# PinballBumper_DaughterBoard.net
KiCad netlist of a schematic drawn in EAGLE
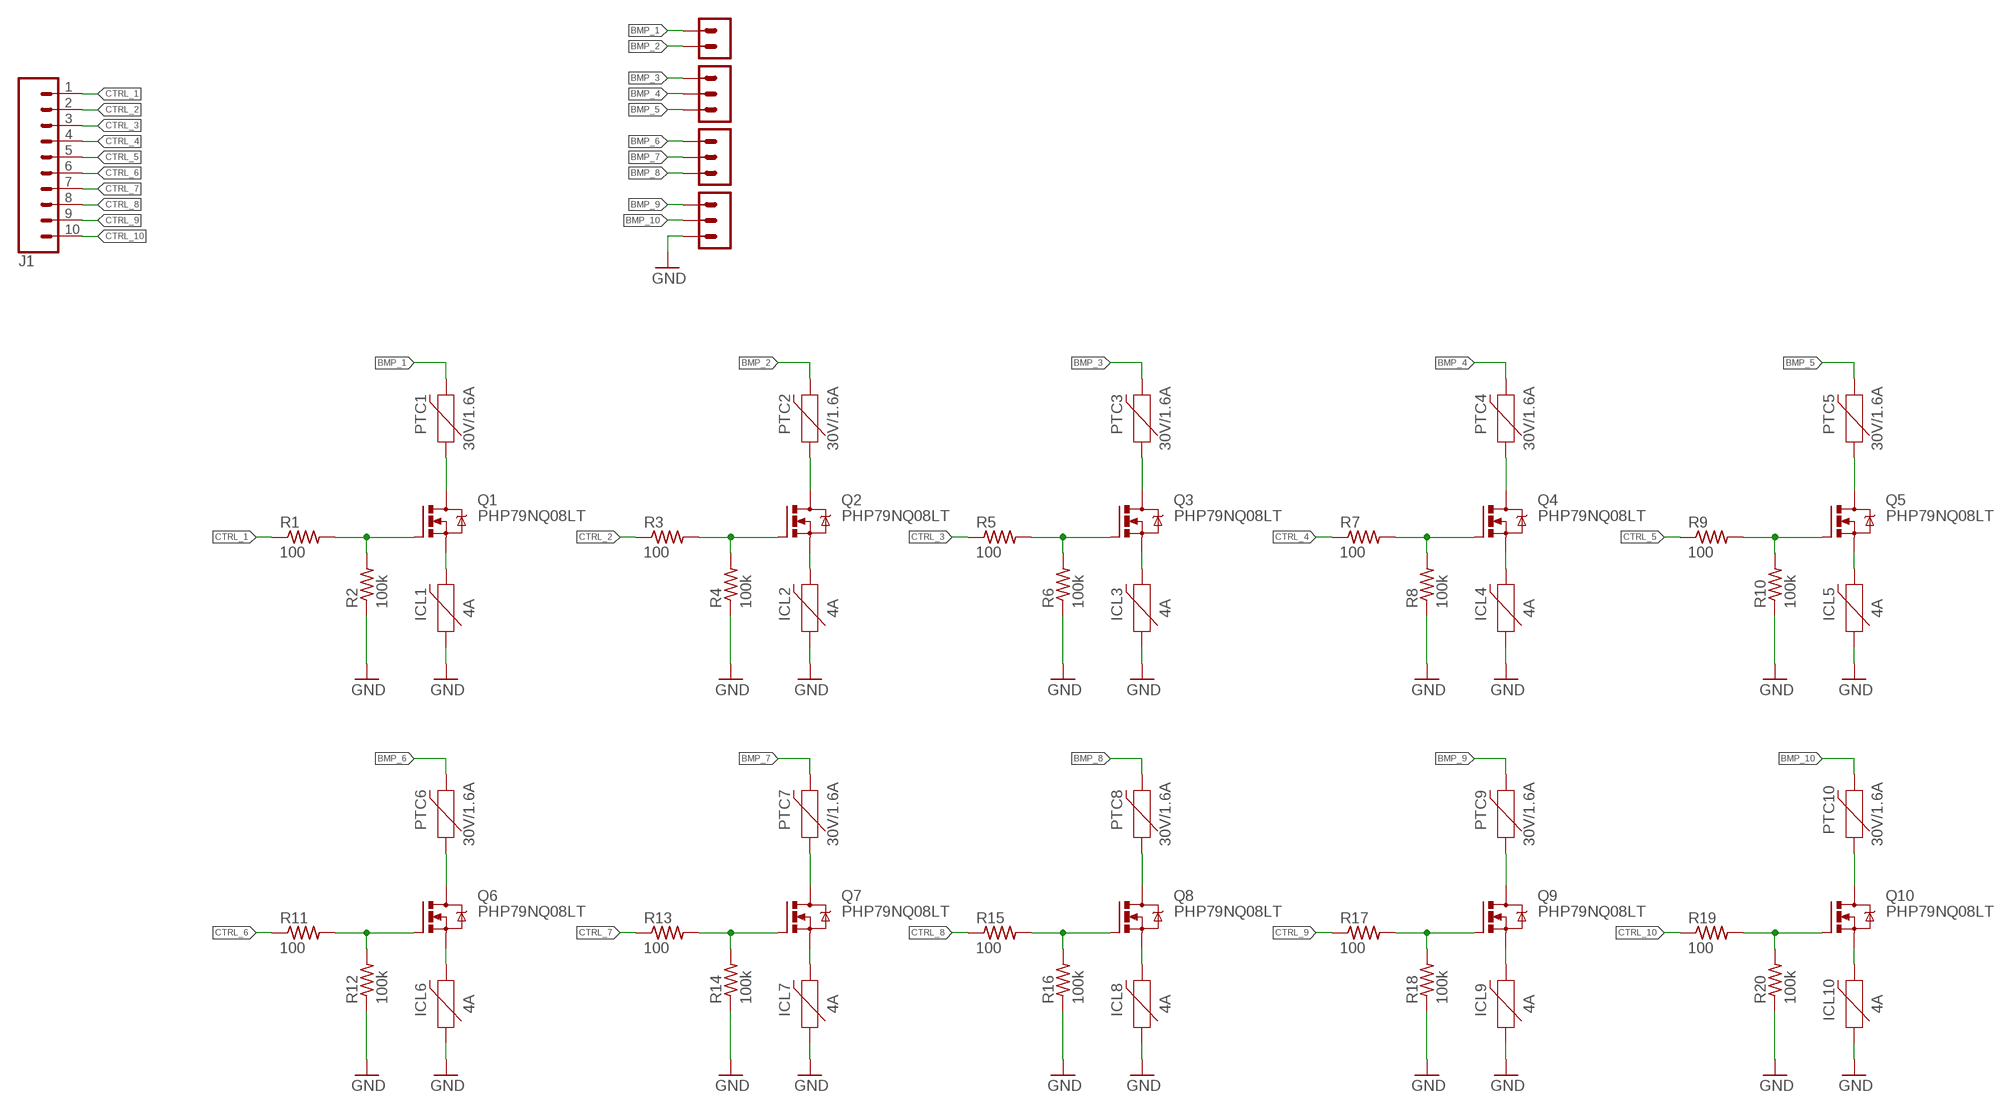
[diagram p0: schematic, sheet 1]

(export (version "E")
  (design (tool "Eeschema 10.0.6"))
  (components
    (comp (ref "ICL1")
      (value "4A")
      (footprint "eagle-import:PTH")
      (libsource (lib "eagle-import") (part "PPTC_PTH"))
    )
    (comp (ref "ICL2")
      (value "4A")
      (footprint "eagle-import:PTH")
      (libsource (lib "eagle-import") (part "PPTC_PTH"))
    )
    (comp (ref "ICL3")
      (value "4A")
      (footprint "eagle-import:PTH")
      (libsource (lib "eagle-import") (part "PPTC_PTH"))
    )
    (comp (ref "ICL4")
      (value "4A")
      (footprint "eagle-import:PTH")
      (libsource (lib "eagle-import") (part "PPTC_PTH"))
    )
    (comp (ref "ICL5")
      (value "4A")
      (footprint "eagle-import:PTH")
      (libsource (lib "eagle-import") (part "PPTC_PTH"))
    )
    (comp (ref "ICL6")
      (value "4A")
      (footprint "eagle-import:PTH")
      (libsource (lib "eagle-import") (part "PPTC_PTH"))
    )
    (comp (ref "ICL7")
      (value "4A")
      (footprint "eagle-import:PTH")
      (libsource (lib "eagle-import") (part "PPTC_PTH"))
    )
    (comp (ref "ICL8")
      (value "4A")
      (footprint "eagle-import:PTH")
      (libsource (lib "eagle-import") (part "PPTC_PTH"))
    )
    (comp (ref "ICL9")
      (value "4A")
      (footprint "eagle-import:PTH")
      (libsource (lib "eagle-import") (part "PPTC_PTH"))
    )
    (comp (ref "ICL10")
      (value "4A")
      (footprint "eagle-import:PTH")
      (libsource (lib "eagle-import") (part "PPTC_PTH"))
    )
    (comp (ref "J1")
      (value "CONN_10\"")
      (footprint "eagle-import:1X10")
      (libsource (lib "eagle-import") (part "CONN_10{dblquote}"))
    )
    (comp (ref "PTC1")
      (value "30V/1.6A")
      (footprint "eagle-import:PTH")
      (libsource (lib "eagle-import") (part "PPTC_PTH"))
    )
    (comp (ref "PTC2")
      (value "30V/1.6A")
      (footprint "eagle-import:PTH")
      (libsource (lib "eagle-import") (part "PPTC_PTH"))
    )
    (comp (ref "PTC3")
      (value "30V/1.6A")
      (footprint "eagle-import:PTH")
      (libsource (lib "eagle-import") (part "PPTC_PTH"))
    )
    (comp (ref "PTC4")
      (value "30V/1.6A")
      (footprint "eagle-import:PTH")
      (libsource (lib "eagle-import") (part "PPTC_PTH"))
    )
    (comp (ref "PTC5")
      (value "30V/1.6A")
      (footprint "eagle-import:PTH")
      (libsource (lib "eagle-import") (part "PPTC_PTH"))
    )
    (comp (ref "PTC6")
      (value "30V/1.6A")
      (footprint "eagle-import:PTH")
      (libsource (lib "eagle-import") (part "PPTC_PTH"))
    )
    (comp (ref "PTC7")
      (value "30V/1.6A")
      (footprint "eagle-import:PTH")
      (libsource (lib "eagle-import") (part "PPTC_PTH"))
    )
    (comp (ref "PTC8")
      (value "30V/1.6A")
      (footprint "eagle-import:PTH")
      (libsource (lib "eagle-import") (part "PPTC_PTH"))
    )
    (comp (ref "PTC9")
      (value "30V/1.6A")
      (footprint "eagle-import:PTH")
      (libsource (lib "eagle-import") (part "PPTC_PTH"))
    )
    (comp (ref "PTC10")
      (value "30V/1.6A")
      (footprint "eagle-import:PTH")
      (libsource (lib "eagle-import") (part "PPTC_PTH"))
    )
    (comp (ref "Q1")
      (value "PHP79NQ08LT")
      (footprint "eagle-import:TO220BV")
      (libsource (lib "eagle-import") (part "IRF740"))
    )
    (comp (ref "Q2")
      (value "PHP79NQ08LT")
      (footprint "eagle-import:TO220BV")
      (libsource (lib "eagle-import") (part "IRF740"))
    )
    (comp (ref "Q3")
      (value "PHP79NQ08LT")
      (footprint "eagle-import:TO220BV")
      (libsource (lib "eagle-import") (part "IRF740"))
    )
    (comp (ref "Q4")
      (value "PHP79NQ08LT")
      (footprint "eagle-import:TO220BV")
      (libsource (lib "eagle-import") (part "IRF740"))
    )
    (comp (ref "Q5")
      (value "PHP79NQ08LT")
      (footprint "eagle-import:TO220BV")
      (libsource (lib "eagle-import") (part "IRF740"))
    )
    (comp (ref "Q6")
      (value "PHP79NQ08LT")
      (footprint "eagle-import:TO220BV")
      (libsource (lib "eagle-import") (part "IRF740"))
    )
    (comp (ref "Q7")
      (value "PHP79NQ08LT")
      (footprint "eagle-import:TO220BV")
      (libsource (lib "eagle-import") (part "IRF740"))
    )
    (comp (ref "Q8")
      (value "PHP79NQ08LT")
      (footprint "eagle-import:TO220BV")
      (libsource (lib "eagle-import") (part "IRF740"))
    )
    (comp (ref "Q9")
      (value "PHP79NQ08LT")
      (footprint "eagle-import:TO220BV")
      (libsource (lib "eagle-import") (part "IRF740"))
    )
    (comp (ref "Q10")
      (value "PHP79NQ08LT")
      (footprint "eagle-import:TO220BV")
      (libsource (lib "eagle-import") (part "IRF740"))
    )
    (comp (ref "R1")
      (value "100")
      (footprint "eagle-import:0204_7")
      (libsource (lib "eagle-import") (part "R-US_0204/7"))
    )
    (comp (ref "R2")
      (value "100k")
      (footprint "eagle-import:0204_7")
      (libsource (lib "eagle-import") (part "R-US_0204/7"))
    )
    (comp (ref "R3")
      (value "100")
      (footprint "eagle-import:0204_7")
      (libsource (lib "eagle-import") (part "R-US_0204/7"))
    )
    (comp (ref "R4")
      (value "100k")
      (footprint "eagle-import:0204_7")
      (libsource (lib "eagle-import") (part "R-US_0204/7"))
    )
    (comp (ref "R5")
      (value "100")
      (footprint "eagle-import:0204_7")
      (libsource (lib "eagle-import") (part "R-US_0204/7"))
    )
    (comp (ref "R6")
      (value "100k")
      (footprint "eagle-import:0204_7")
      (libsource (lib "eagle-import") (part "R-US_0204/7"))
    )
    (comp (ref "R7")
      (value "100")
      (footprint "eagle-import:0204_7")
      (libsource (lib "eagle-import") (part "R-US_0204/7"))
    )
    (comp (ref "R8")
      (value "100k")
      (footprint "eagle-import:0204_7")
      (libsource (lib "eagle-import") (part "R-US_0204/7"))
    )
    (comp (ref "R9")
      (value "100")
      (footprint "eagle-import:0204_7")
      (libsource (lib "eagle-import") (part "R-US_0204/7"))
    )
    (comp (ref "R10")
      (value "100k")
      (footprint "eagle-import:0204_7")
      (libsource (lib "eagle-import") (part "R-US_0204/7"))
    )
    (comp (ref "R11")
      (value "100")
      (footprint "eagle-import:0204_7")
      (libsource (lib "eagle-import") (part "R-US_0204/7"))
    )
    (comp (ref "R12")
      (value "100k")
      (footprint "eagle-import:0204_7")
      (libsource (lib "eagle-import") (part "R-US_0204/7"))
    )
    (comp (ref "R13")
      (value "100")
      (footprint "eagle-import:0204_7")
      (libsource (lib "eagle-import") (part "R-US_0204/7"))
    )
    (comp (ref "R14")
      (value "100k")
      (footprint "eagle-import:0204_7")
      (libsource (lib "eagle-import") (part "R-US_0204/7"))
    )
    (comp (ref "R15")
      (value "100")
      (footprint "eagle-import:0204_7")
      (libsource (lib "eagle-import") (part "R-US_0204/7"))
    )
    (comp (ref "R16")
      (value "100k")
      (footprint "eagle-import:0204_7")
      (libsource (lib "eagle-import") (part "R-US_0204/7"))
    )
    (comp (ref "R17")
      (value "100")
      (footprint "eagle-import:0204_7")
      (libsource (lib "eagle-import") (part "R-US_0204/7"))
    )
    (comp (ref "R18")
      (value "100k")
      (footprint "eagle-import:0204_7")
      (libsource (lib "eagle-import") (part "R-US_0204/7"))
    )
    (comp (ref "R19")
      (value "100")
      (footprint "eagle-import:0204_7")
      (libsource (lib "eagle-import") (part "R-US_0204/7"))
    )
    (comp (ref "R20")
      (value "100k")
      (footprint "eagle-import:0204_7")
      (libsource (lib "eagle-import") (part "R-US_0204/7"))
    )
    (comp (ref "U$1")
      (value "BIG_TERMINAL_2PINBIG")
      (footprint "eagle-import:BIG_TERMINAL_2PIN")
      (libsource (lib "eagle-import") (part "BIG_TERMINAL_2PINBIG"))
    )
    (comp (ref "U$2")
      (value "BIG_TERMINAL_3PINBIG")
      (footprint "eagle-import:BIG_TERMINAL_3PIN")
      (libsource (lib "eagle-import") (part "BIG_TERMINAL_3PINBIG"))
    )
    (comp (ref "U$3")
      (value "BIG_TERMINAL_3PINBIG")
      (footprint "eagle-import:BIG_TERMINAL_3PIN")
      (libsource (lib "eagle-import") (part "BIG_TERMINAL_3PINBIG"))
    )
    (comp (ref "U$4")
      (value "BIG_TERMINAL_3PINBIG")
      (footprint "eagle-import:BIG_TERMINAL_3PIN")
      (libsource (lib "eagle-import") (part "BIG_TERMINAL_3PINBIG"))
    )
  )
  (nets
    (net (code "1") (name "BMP_1") (class "Default")
      (node (ref "PTC1") (pin "P$2") (pinfunction "2_P$2") (pintype "bidirectional"))
      (node (ref "U$1") (pin "P$1") (pinfunction "P$1_P$1") (pintype "bidirectional"))
    )
    (net (code "2") (name "BMP_2") (class "Default")
      (node (ref "PTC2") (pin "P$2") (pinfunction "2_P$2") (pintype "bidirectional"))
      (node (ref "U$1") (pin "P$2") (pinfunction "P$2_P$2") (pintype "bidirectional"))
    )
    (net (code "3") (name "BMP_3") (class "Default")
      (node (ref "PTC3") (pin "P$2") (pinfunction "2_P$2") (pintype "bidirectional"))
      (node (ref "U$2") (pin "1") (pinfunction "1_1") (pintype "bidirectional"))
    )
    (net (code "4") (name "BMP_4") (class "Default")
      (node (ref "PTC4") (pin "P$2") (pinfunction "2_P$2") (pintype "bidirectional"))
      (node (ref "U$2") (pin "2") (pinfunction "2_2") (pintype "bidirectional"))
    )
    (net (code "5") (name "BMP_5") (class "Default")
      (node (ref "PTC5") (pin "P$2") (pinfunction "2_P$2") (pintype "bidirectional"))
      (node (ref "U$2") (pin "3") (pinfunction "3_3") (pintype "bidirectional"))
    )
    (net (code "6") (name "BMP_6") (class "Default")
      (node (ref "PTC6") (pin "P$2") (pinfunction "2_P$2") (pintype "bidirectional"))
      (node (ref "U$3") (pin "1") (pinfunction "1_1") (pintype "bidirectional"))
    )
    (net (code "7") (name "BMP_7") (class "Default")
      (node (ref "PTC7") (pin "P$2") (pinfunction "2_P$2") (pintype "bidirectional"))
      (node (ref "U$3") (pin "2") (pinfunction "2_2") (pintype "bidirectional"))
    )
    (net (code "8") (name "BMP_8") (class "Default")
      (node (ref "PTC8") (pin "P$2") (pinfunction "2_P$2") (pintype "bidirectional"))
      (node (ref "U$3") (pin "3") (pinfunction "3_3") (pintype "bidirectional"))
    )
    (net (code "9") (name "BMP_9") (class "Default")
      (node (ref "PTC9") (pin "P$2") (pinfunction "2_P$2") (pintype "bidirectional"))
      (node (ref "U$4") (pin "1") (pinfunction "1_1") (pintype "bidirectional"))
    )
    (net (code "10") (name "BMP_10") (class "Default")
      (node (ref "PTC10") (pin "P$2") (pinfunction "2_P$2") (pintype "bidirectional"))
      (node (ref "U$4") (pin "2") (pinfunction "2_2") (pintype "bidirectional"))
    )
    (net (code "11") (name "CTRL_1") (class "Default")
      (node (ref "J1") (pin "1") (pinfunction "1_1") (pintype "passive"))
      (node (ref "R1") (pin "1") (pinfunction "1_1") (pintype "passive"))
    )
    (net (code "12") (name "CTRL_2") (class "Default")
      (node (ref "J1") (pin "2") (pinfunction "2_2") (pintype "passive"))
      (node (ref "R3") (pin "1") (pinfunction "1_1") (pintype "passive"))
    )
    (net (code "13") (name "CTRL_3") (class "Default")
      (node (ref "J1") (pin "3") (pinfunction "3_3") (pintype "passive"))
      (node (ref "R5") (pin "1") (pinfunction "1_1") (pintype "passive"))
    )
    (net (code "14") (name "CTRL_4") (class "Default")
      (node (ref "J1") (pin "4") (pinfunction "4_4") (pintype "passive"))
      (node (ref "R7") (pin "1") (pinfunction "1_1") (pintype "passive"))
    )
    (net (code "15") (name "CTRL_5") (class "Default")
      (node (ref "J1") (pin "5") (pinfunction "5_5") (pintype "passive"))
      (node (ref "R9") (pin "1") (pinfunction "1_1") (pintype "passive"))
    )
    (net (code "16") (name "CTRL_6") (class "Default")
      (node (ref "J1") (pin "6") (pinfunction "6_6") (pintype "passive"))
      (node (ref "R11") (pin "1") (pinfunction "1_1") (pintype "passive"))
    )
    (net (code "17") (name "CTRL_7") (class "Default")
      (node (ref "J1") (pin "7") (pinfunction "7_7") (pintype "passive"))
      (node (ref "R13") (pin "1") (pinfunction "1_1") (pintype "passive"))
    )
    (net (code "18") (name "CTRL_8") (class "Default")
      (node (ref "J1") (pin "8") (pinfunction "8_8") (pintype "passive"))
      (node (ref "R15") (pin "1") (pinfunction "1_1") (pintype "passive"))
    )
    (net (code "19") (name "CTRL_9") (class "Default")
      (node (ref "J1") (pin "9") (pinfunction "9_9") (pintype "passive"))
      (node (ref "R17") (pin "1") (pinfunction "1_1") (pintype "passive"))
    )
    (net (code "20") (name "CTRL_10") (class "Default")
      (node (ref "J1") (pin "10") (pinfunction "10_10") (pintype "passive"))
      (node (ref "R19") (pin "1") (pinfunction "1_1") (pintype "passive"))
    )
    (net (code "21") (name "GND") (class "Default")
      (node (ref "ICL1") (pin "P$1") (pinfunction "1_P$1") (pintype "bidirectional"))
      (node (ref "ICL10") (pin "P$1") (pinfunction "1_P$1") (pintype "bidirectional"))
      (node (ref "ICL2") (pin "P$1") (pinfunction "1_P$1") (pintype "bidirectional"))
      (node (ref "ICL3") (pin "P$1") (pinfunction "1_P$1") (pintype "bidirectional"))
      (node (ref "ICL4") (pin "P$1") (pinfunction "1_P$1") (pintype "bidirectional"))
      (node (ref "ICL5") (pin "P$1") (pinfunction "1_P$1") (pintype "bidirectional"))
      (node (ref "ICL6") (pin "P$1") (pinfunction "1_P$1") (pintype "bidirectional"))
      (node (ref "ICL7") (pin "P$1") (pinfunction "1_P$1") (pintype "bidirectional"))
      (node (ref "ICL8") (pin "P$1") (pinfunction "1_P$1") (pintype "bidirectional"))
      (node (ref "ICL9") (pin "P$1") (pinfunction "1_P$1") (pintype "bidirectional"))
      (node (ref "R10") (pin "1") (pinfunction "1_1") (pintype "passive"))
      (node (ref "R12") (pin "1") (pinfunction "1_1") (pintype "passive"))
      (node (ref "R14") (pin "1") (pinfunction "1_1") (pintype "passive"))
      (node (ref "R16") (pin "1") (pinfunction "1_1") (pintype "passive"))
      (node (ref "R18") (pin "1") (pinfunction "1_1") (pintype "passive"))
      (node (ref "R2") (pin "1") (pinfunction "1_1") (pintype "passive"))
      (node (ref "R20") (pin "1") (pinfunction "1_1") (pintype "passive"))
      (node (ref "R4") (pin "1") (pinfunction "1_1") (pintype "passive"))
      (node (ref "R6") (pin "1") (pinfunction "1_1") (pintype "passive"))
      (node (ref "R8") (pin "1") (pinfunction "1_1") (pintype "passive"))
      (node (ref "U$4") (pin "3") (pinfunction "3_3") (pintype "bidirectional"))
    )
    (net (code "22") (name "Net-(ICL1-2)") (class "Default")
      (node (ref "ICL1") (pin "P$2") (pinfunction "2_P$2") (pintype "bidirectional"))
      (node (ref "Q1") (pin "S") (pinfunction "S_S") (pintype "passive"))
    )
    (net (code "23") (name "Net-(ICL2-2)") (class "Default")
      (node (ref "ICL2") (pin "P$2") (pinfunction "2_P$2") (pintype "bidirectional"))
      (node (ref "Q2") (pin "S") (pinfunction "S_S") (pintype "passive"))
    )
    (net (code "24") (name "Net-(ICL3-2)") (class "Default")
      (node (ref "ICL3") (pin "P$2") (pinfunction "2_P$2") (pintype "bidirectional"))
      (node (ref "Q3") (pin "S") (pinfunction "S_S") (pintype "passive"))
    )
    (net (code "25") (name "Net-(ICL4-2)") (class "Default")
      (node (ref "ICL4") (pin "P$2") (pinfunction "2_P$2") (pintype "bidirectional"))
      (node (ref "Q4") (pin "S") (pinfunction "S_S") (pintype "passive"))
    )
    (net (code "26") (name "Net-(ICL5-2)") (class "Default")
      (node (ref "ICL5") (pin "P$2") (pinfunction "2_P$2") (pintype "bidirectional"))
      (node (ref "Q5") (pin "S") (pinfunction "S_S") (pintype "passive"))
    )
    (net (code "27") (name "Net-(ICL6-2)") (class "Default")
      (node (ref "ICL6") (pin "P$2") (pinfunction "2_P$2") (pintype "bidirectional"))
      (node (ref "Q6") (pin "S") (pinfunction "S_S") (pintype "passive"))
    )
    (net (code "28") (name "Net-(ICL7-2)") (class "Default")
      (node (ref "ICL7") (pin "P$2") (pinfunction "2_P$2") (pintype "bidirectional"))
      (node (ref "Q7") (pin "S") (pinfunction "S_S") (pintype "passive"))
    )
    (net (code "29") (name "Net-(ICL8-2)") (class "Default")
      (node (ref "ICL8") (pin "P$2") (pinfunction "2_P$2") (pintype "bidirectional"))
      (node (ref "Q8") (pin "S") (pinfunction "S_S") (pintype "passive"))
    )
    (net (code "30") (name "Net-(ICL9-2)") (class "Default")
      (node (ref "ICL9") (pin "P$2") (pinfunction "2_P$2") (pintype "bidirectional"))
      (node (ref "Q9") (pin "S") (pinfunction "S_S") (pintype "passive"))
    )
    (net (code "31") (name "Net-(ICL10-2)") (class "Default")
      (node (ref "ICL10") (pin "P$2") (pinfunction "2_P$2") (pintype "bidirectional"))
      (node (ref "Q10") (pin "S") (pinfunction "S_S") (pintype "passive"))
    )
    (net (code "32") (name "Net-(PTC1-1)") (class "Default")
      (node (ref "PTC1") (pin "P$1") (pinfunction "1_P$1") (pintype "bidirectional"))
      (node (ref "Q1") (pin "D") (pinfunction "D_D") (pintype "passive"))
    )
    (net (code "33") (name "Net-(PTC2-1)") (class "Default")
      (node (ref "PTC2") (pin "P$1") (pinfunction "1_P$1") (pintype "bidirectional"))
      (node (ref "Q2") (pin "D") (pinfunction "D_D") (pintype "passive"))
    )
    (net (code "34") (name "Net-(PTC3-1)") (class "Default")
      (node (ref "PTC3") (pin "P$1") (pinfunction "1_P$1") (pintype "bidirectional"))
      (node (ref "Q3") (pin "D") (pinfunction "D_D") (pintype "passive"))
    )
    (net (code "35") (name "Net-(PTC4-1)") (class "Default")
      (node (ref "PTC4") (pin "P$1") (pinfunction "1_P$1") (pintype "bidirectional"))
      (node (ref "Q4") (pin "D") (pinfunction "D_D") (pintype "passive"))
    )
    (net (code "36") (name "Net-(PTC5-1)") (class "Default")
      (node (ref "PTC5") (pin "P$1") (pinfunction "1_P$1") (pintype "bidirectional"))
      (node (ref "Q5") (pin "D") (pinfunction "D_D") (pintype "passive"))
    )
    (net (code "37") (name "Net-(PTC6-1)") (class "Default")
      (node (ref "PTC6") (pin "P$1") (pinfunction "1_P$1") (pintype "bidirectional"))
      (node (ref "Q6") (pin "D") (pinfunction "D_D") (pintype "passive"))
    )
    (net (code "38") (name "Net-(PTC7-1)") (class "Default")
      (node (ref "PTC7") (pin "P$1") (pinfunction "1_P$1") (pintype "bidirectional"))
      (node (ref "Q7") (pin "D") (pinfunction "D_D") (pintype "passive"))
    )
    (net (code "39") (name "Net-(PTC8-1)") (class "Default")
      (node (ref "PTC8") (pin "P$1") (pinfunction "1_P$1") (pintype "bidirectional"))
      (node (ref "Q8") (pin "D") (pinfunction "D_D") (pintype "passive"))
    )
    (net (code "40") (name "Net-(PTC9-1)") (class "Default")
      (node (ref "PTC9") (pin "P$1") (pinfunction "1_P$1") (pintype "bidirectional"))
      (node (ref "Q9") (pin "D") (pinfunction "D_D") (pintype "passive"))
    )
    (net (code "41") (name "Net-(PTC10-1)") (class "Default")
      (node (ref "PTC10") (pin "P$1") (pinfunction "1_P$1") (pintype "bidirectional"))
      (node (ref "Q10") (pin "D") (pinfunction "D_D") (pintype "passive"))
    )
    (net (code "42") (name "Net-(Q1-PadG)") (class "Default")
      (node (ref "Q1") (pin "G") (pinfunction "G_G") (pintype "passive"))
      (node (ref "R1") (pin "2") (pinfunction "2_2") (pintype "passive"))
      (node (ref "R2") (pin "2") (pinfunction "2_2") (pintype "passive"))
    )
    (net (code "43") (name "Net-(Q2-PadG)") (class "Default")
      (node (ref "Q2") (pin "G") (pinfunction "G_G") (pintype "passive"))
      (node (ref "R3") (pin "2") (pinfunction "2_2") (pintype "passive"))
      (node (ref "R4") (pin "2") (pinfunction "2_2") (pintype "passive"))
    )
    (net (code "44") (name "Net-(Q3-PadG)") (class "Default")
      (node (ref "Q3") (pin "G") (pinfunction "G_G") (pintype "passive"))
      (node (ref "R5") (pin "2") (pinfunction "2_2") (pintype "passive"))
      (node (ref "R6") (pin "2") (pinfunction "2_2") (pintype "passive"))
    )
    (net (code "45") (name "Net-(Q4-PadG)") (class "Default")
      (node (ref "Q4") (pin "G") (pinfunction "G_G") (pintype "passive"))
      (node (ref "R7") (pin "2") (pinfunction "2_2") (pintype "passive"))
      (node (ref "R8") (pin "2") (pinfunction "2_2") (pintype "passive"))
    )
    (net (code "46") (name "Net-(Q5-PadG)") (class "Default")
      (node (ref "Q5") (pin "G") (pinfunction "G_G") (pintype "passive"))
      (node (ref "R10") (pin "2") (pinfunction "2_2") (pintype "passive"))
      (node (ref "R9") (pin "2") (pinfunction "2_2") (pintype "passive"))
    )
    (net (code "47") (name "Net-(Q6-PadG)") (class "Default")
      (node (ref "Q6") (pin "G") (pinfunction "G_G") (pintype "passive"))
      (node (ref "R11") (pin "2") (pinfunction "2_2") (pintype "passive"))
      (node (ref "R12") (pin "2") (pinfunction "2_2") (pintype "passive"))
    )
    (net (code "48") (name "Net-(Q7-PadG)") (class "Default")
      (node (ref "Q7") (pin "G") (pinfunction "G_G") (pintype "passive"))
      (node (ref "R13") (pin "2") (pinfunction "2_2") (pintype "passive"))
      (node (ref "R14") (pin "2") (pinfunction "2_2") (pintype "passive"))
    )
    (net (code "49") (name "Net-(Q8-PadG)") (class "Default")
      (node (ref "Q8") (pin "G") (pinfunction "G_G") (pintype "passive"))
      (node (ref "R15") (pin "2") (pinfunction "2_2") (pintype "passive"))
      (node (ref "R16") (pin "2") (pinfunction "2_2") (pintype "passive"))
    )
    (net (code "50") (name "Net-(Q9-PadG)") (class "Default")
      (node (ref "Q9") (pin "G") (pinfunction "G_G") (pintype "passive"))
      (node (ref "R17") (pin "2") (pinfunction "2_2") (pintype "passive"))
      (node (ref "R18") (pin "2") (pinfunction "2_2") (pintype "passive"))
    )
    (net (code "51") (name "Net-(Q10-PadG)") (class "Default")
      (node (ref "Q10") (pin "G") (pinfunction "G_G") (pintype "passive"))
      (node (ref "R19") (pin "2") (pinfunction "2_2") (pintype "passive"))
      (node (ref "R20") (pin "2") (pinfunction "2_2") (pintype "passive"))
    )
  )
)
